# MicrobitBoardExtend.net
KiCad netlist of a schematic drawn in Altium Designer
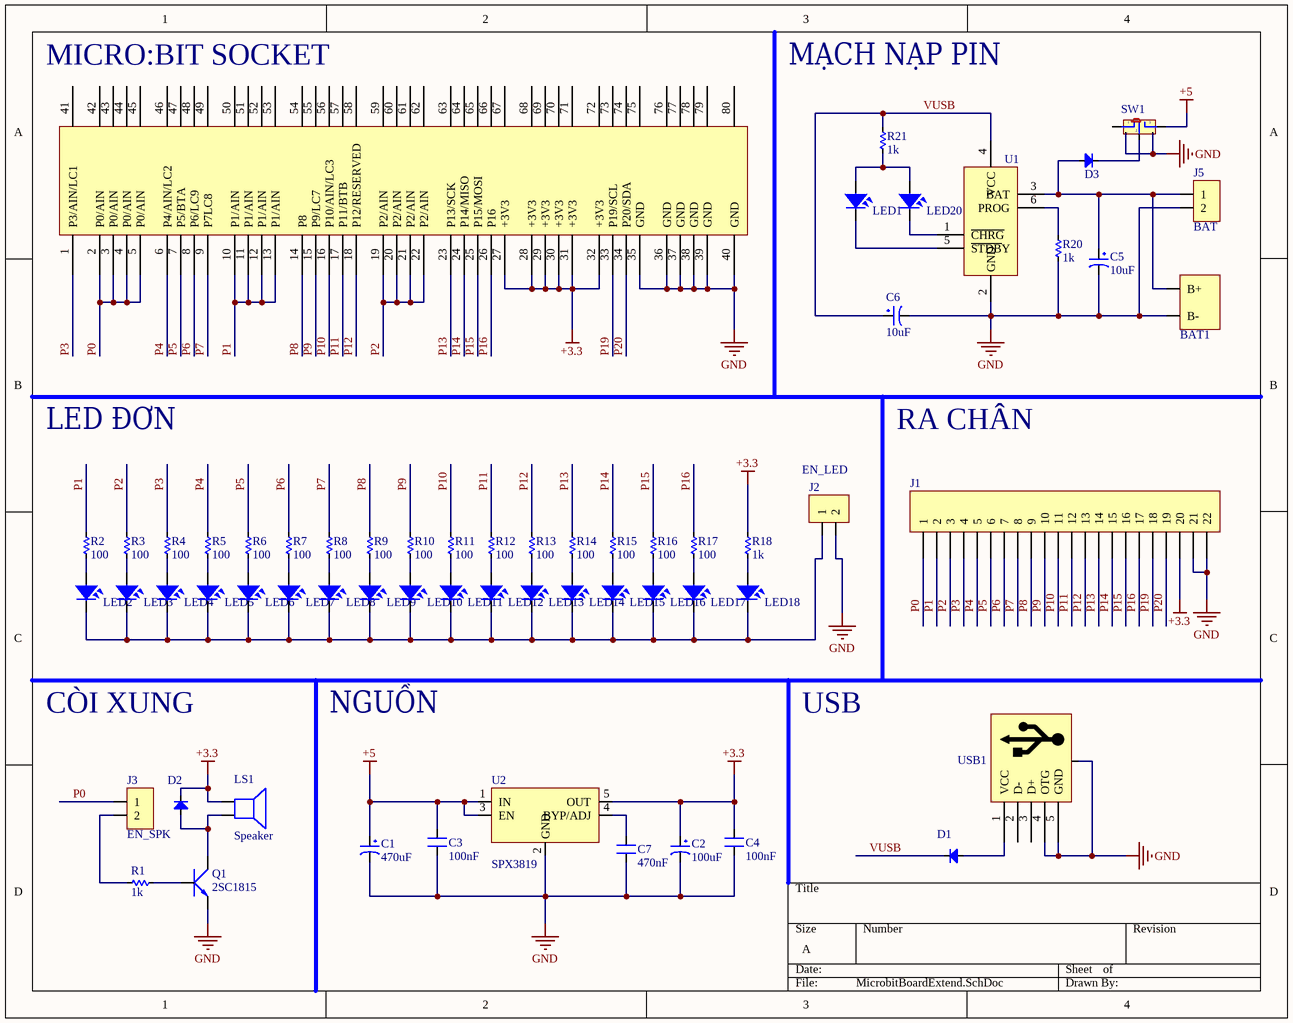
[diagram p0: MicrobitBoardExtend.SchDoc]

(export (version "E")
  (design (tool "Eeschema 10.0.6"))
  (components
    (comp (ref "BAT1")
      (value "BATERRY SOCKET")
      (footprint "BAT_SOCKET")
      (libsource (lib "User") (part "BAT_SOCKET"))
    )
    (comp (ref "BBC1")
      (value "BBC_SOCKET")
      (footprint "BBC_SK_DIP")
      (libsource (lib "microbit") (part "BBC_SOCKET"))
    )
    (comp (ref "C1")
      (value "470uF")
      (footprint "tu tantalum smd7343")
      (description "Dán")
      (libsource (lib "THU VIEN SCH_04042017_1") (part "Tu tantalum 470uF 10V SMD7343"))
    )
    (comp (ref "C2")
      (value "100uF")
      (footprint "tu tantalum smd3528")
      (description "Dán")
      (libsource (lib "THU VIEN SCH_04042017_1") (part "Tu tantalum 100uF 6.3V SMD3528"))
    )
    (comp (ref "C3") (value "100nF") (footprint "CN-SMD-0805") (libsource (lib "LIBRARY") (part "CN")))
    (comp (ref "C4") (value "100nF") (footprint "CN-SMD-0805") (libsource (lib "LIBRARY") (part "CN")))
    (comp (ref "C5")
      (value "10uF")
      (footprint "tu tantalum smd3528")
      (description "Dán")
      (libsource (lib "") (part "Tu tantalum 10uF 16V SMD3528_1"))
    )
    (comp (ref "C6")
      (value "10uF")
      (footprint "tu tantalum smd3528")
      (description "Dán")
      (libsource (lib "THU VIEN SCH_04042017_1") (part "Tu tantalum 10uF 16V SMD3528"))
    )
    (comp (ref "C7") (value "470nF") (footprint "CN-SMD-0805") (libsource (lib "LIBRARY") (part "CN")))
    (comp (ref "D1")
      (value "SS34")
      (footprint "DIO-SMD-123")
      (description "Default Diode")
      (fields (field (name "PUBLISHER") "Altium Limited"))
      (libsource (lib "LIBRARY") (part "Diode SMD"))
    )
    (comp (ref "D2")
      (value "SS34")
      (footprint "DIO-SMD-123")
      (description "Default Diode")
      (fields (field (name "PUBLISHER") "Altium Limited"))
      (libsource (lib "LIBRARY") (part "Diode SMD"))
    )
    (comp (ref "D3")
      (value "SS34")
      (footprint "DIO-SMD-123")
      (description "Default Diode")
      (fields (field (name "PUBLISHER") "Altium Limited"))
      (libsource (lib "LIBRARY") (part "Diode SMD"))
    )
    (comp (ref "J1")
      (value "JP22")
      (footprint "JP22-D1T")
      (description "WR-PHD 2.54 mm Angled Socket Header")
      (fields
        (field (name "MANUFACTURER") "Würth Elektronik eiSos GmbH")
        (field (name "PARTNO") "613022143121")
        (field (name "CREATED BY") "Karrer Zheng")
      )
      (libsource (lib "LIBRARY") (part "JP22"))
    )
    (comp (ref "J2")
      (value "EN_LED")
      (footprint "JP2-CLOSED")
      (description "WR-PHD 2.54 mm Angled Socket Header")
      (fields
        (field (name "MANUFACTURER") "Würth Elektronik eiSos GmbH")
        (field (name "PARTNO") "613002143121")
        (field (name "CREATED BY") "Karrer Zheng")
      )
      (libsource (lib "LIBRARY") (part "JP2"))
    )
    (comp (ref "J3")
      (value "EN_SPK")
      (footprint "JP2-CLOSED")
      (description "WR-PHD 2.54 mm Angled Socket Header")
      (fields
        (field (name "MANUFACTURER") "Würth Elektronik eiSos GmbH")
        (field (name "PARTNO") "613002143121")
        (field (name "CREATED BY") "Karrer Zheng")
      )
      (libsource (lib "") (part "JP2_1"))
    )
    (comp (ref "J5")
      (value "BAT")
      (footprint "JP2-D1T")
      (description "WR-PHD 2.54 mm Angled Socket Header")
      (fields
        (field (name "MANUFACTURER") "Würth Elektronik eiSos GmbH")
        (field (name "PARTNO") "613002143121")
        (field (name "CREATED BY") "Karrer Zheng")
      )
      (libsource (lib "") (part "JP2_1"))
    )
    (comp (ref "LED1") (value "F") (footprint "LED-0805-Blue") (libsource (lib "LIBRARY") (part "LED SMD")))
    (comp (ref "LED2")
      (value "LED")
      (footprint "LED-3MM-BLUE")
      (description "LED Single colour Green and Red")
      (libsource (lib "LIBRARY") (part "LED"))
    )
    (comp (ref "LED3")
      (value "LED")
      (footprint "LED-3MM-BLUE")
      (description "LED Single colour Green and Red")
      (libsource (lib "LIBRARY") (part "LED"))
    )
    (comp (ref "LED4")
      (value "LED")
      (footprint "LED-3MM-BLUE")
      (description "LED Single colour Green and Red")
      (libsource (lib "LIBRARY") (part "LED"))
    )
    (comp (ref "LED5")
      (value "LED")
      (footprint "LED-3MM-BLUE")
      (description "LED Single colour Green and Red")
      (libsource (lib "LIBRARY") (part "LED"))
    )
    (comp (ref "LED6")
      (value "LED")
      (footprint "LED-3MM-BLUE")
      (description "LED Single colour Green and Red")
      (libsource (lib "LIBRARY") (part "LED"))
    )
    (comp (ref "LED7")
      (value "LED")
      (footprint "LED-3MM-BLUE")
      (description "LED Single colour Green and Red")
      (libsource (lib "LIBRARY") (part "LED"))
    )
    (comp (ref "LED8")
      (value "LED")
      (footprint "LED-3MM-BLUE")
      (description "LED Single colour Green and Red")
      (libsource (lib "LIBRARY") (part "LED"))
    )
    (comp (ref "LED9")
      (value "LED")
      (footprint "LED-3MM-BLUE")
      (description "LED Single colour Green and Red")
      (libsource (lib "LIBRARY") (part "LED"))
    )
    (comp (ref "LED10")
      (value "LED")
      (footprint "LED-3MM-BLUE")
      (description "LED Single colour Green and Red")
      (libsource (lib "LIBRARY") (part "LED"))
    )
    (comp (ref "LED11")
      (value "LED")
      (footprint "LED-3MM-BLUE")
      (description "LED Single colour Green and Red")
      (libsource (lib "LIBRARY") (part "LED"))
    )
    (comp (ref "LED12")
      (value "LED")
      (footprint "LED-3MM-BLUE")
      (description "LED Single colour Green and Red")
      (libsource (lib "LIBRARY") (part "LED"))
    )
    (comp (ref "LED13")
      (value "LED")
      (footprint "LED-3MM-BLUE")
      (description "LED Single colour Green and Red")
      (libsource (lib "LIBRARY") (part "LED"))
    )
    (comp (ref "LED14")
      (value "LED")
      (footprint "LED-3MM-BLUE")
      (description "LED Single colour Green and Red")
      (libsource (lib "LIBRARY") (part "LED"))
    )
    (comp (ref "LED15")
      (value "LED")
      (footprint "LED-3MM-BLUE")
      (description "LED Single colour Green and Red")
      (libsource (lib "LIBRARY") (part "LED"))
    )
    (comp (ref "LED16")
      (value "LED")
      (footprint "LED-3MM-BLUE")
      (description "LED Single colour Green and Red")
      (libsource (lib "LIBRARY") (part "LED"))
    )
    (comp (ref "LED17")
      (value "LED")
      (footprint "LED-3MM-BLUE")
      (description "LED Single colour Green and Red")
      (libsource (lib "LIBRARY") (part "LED"))
    )
    (comp (ref "LED18")
      (value "PWR")
      (footprint "LED-0805-Blue")
      (libsource (lib "LIBRARY") (part "LED SMD"))
    )
    (comp (ref "LED20") (value "C") (footprint "LED-0805-Blue") (libsource (lib "LIBRARY") (part "LED SMD")))
    (comp (ref "LS1")
      (value "Speaker")
      (footprint "SPEAKER")
      (description "Loudspeaker")
      (fields (field (name "PUBLISHER") "Altium Limited"))
      (libsource (lib "LIBRARY") (part "Speaker"))
    )
    (comp (ref "Q1")
      (value "2SC1815")
      (footprint "SOT23-321")
      (description "NPN 600mW, ECB")
      (libsource (lib "LIBRARY") (part "2SC1815"))
    )
    (comp (ref "R1")
      (value "1k")
      (footprint "RES-SMD-0805")
      (description "Resistor")
      (fields
        (field (name "MANUFACTURER") "Generic Components")
        (field (name "PUBLISHER") "Altium Hobart Technology Centre")
      )
      (libsource (lib "LIBRARY") (part "Res-SMD"))
    )
    (comp (ref "R2")
      (value "100")
      (footprint "RES-SMD-0805")
      (description "Resistor")
      (fields
        (field (name "MANUFACTURER") "Generic Components")
        (field (name "PUBLISHER") "Altium Hobart Technology Centre")
      )
      (libsource (lib "LIBRARY") (part "Res-SMD"))
    )
    (comp (ref "R3")
      (value "100")
      (footprint "RES-SMD-0805")
      (description "Resistor")
      (fields
        (field (name "MANUFACTURER") "Generic Components")
        (field (name "PUBLISHER") "Altium Hobart Technology Centre")
      )
      (libsource (lib "LIBRARY") (part "Res-SMD"))
    )
    (comp (ref "R4")
      (value "100")
      (footprint "RES-SMD-0805")
      (description "Resistor")
      (fields
        (field (name "MANUFACTURER") "Generic Components")
        (field (name "PUBLISHER") "Altium Hobart Technology Centre")
      )
      (libsource (lib "LIBRARY") (part "Res-SMD"))
    )
    (comp (ref "R5")
      (value "100")
      (footprint "RES-SMD-0805")
      (description "Resistor")
      (fields
        (field (name "MANUFACTURER") "Generic Components")
        (field (name "PUBLISHER") "Altium Hobart Technology Centre")
      )
      (libsource (lib "LIBRARY") (part "Res-SMD"))
    )
    (comp (ref "R6")
      (value "100")
      (footprint "RES-SMD-0805")
      (description "Resistor")
      (fields
        (field (name "MANUFACTURER") "Generic Components")
        (field (name "PUBLISHER") "Altium Hobart Technology Centre")
      )
      (libsource (lib "LIBRARY") (part "Res-SMD"))
    )
    (comp (ref "R7")
      (value "100")
      (footprint "RES-SMD-0805")
      (description "Resistor")
      (fields
        (field (name "MANUFACTURER") "Generic Components")
        (field (name "PUBLISHER") "Altium Hobart Technology Centre")
      )
      (libsource (lib "LIBRARY") (part "Res-SMD"))
    )
    (comp (ref "R8")
      (value "100")
      (footprint "RES-SMD-0805")
      (description "Resistor")
      (fields
        (field (name "MANUFACTURER") "Generic Components")
        (field (name "PUBLISHER") "Altium Hobart Technology Centre")
      )
      (libsource (lib "LIBRARY") (part "Res-SMD"))
    )
    (comp (ref "R9")
      (value "100")
      (footprint "RES-SMD-0805")
      (description "Resistor")
      (fields
        (field (name "MANUFACTURER") "Generic Components")
        (field (name "PUBLISHER") "Altium Hobart Technology Centre")
      )
      (libsource (lib "LIBRARY") (part "Res-SMD"))
    )
    (comp (ref "R10")
      (value "100")
      (footprint "RES-SMD-0805")
      (description "Resistor")
      (fields
        (field (name "MANUFACTURER") "Generic Components")
        (field (name "PUBLISHER") "Altium Hobart Technology Centre")
      )
      (libsource (lib "LIBRARY") (part "Res-SMD"))
    )
    (comp (ref "R11")
      (value "100")
      (footprint "RES-SMD-0805")
      (description "Resistor")
      (fields
        (field (name "MANUFACTURER") "Generic Components")
        (field (name "PUBLISHER") "Altium Hobart Technology Centre")
      )
      (libsource (lib "LIBRARY") (part "Res-SMD"))
    )
    (comp (ref "R12")
      (value "100")
      (footprint "RES-SMD-0805")
      (description "Resistor")
      (fields
        (field (name "MANUFACTURER") "Generic Components")
        (field (name "PUBLISHER") "Altium Hobart Technology Centre")
      )
      (libsource (lib "LIBRARY") (part "Res-SMD"))
    )
    (comp (ref "R13")
      (value "100")
      (footprint "RES-SMD-0805")
      (description "Resistor")
      (fields
        (field (name "MANUFACTURER") "Generic Components")
        (field (name "PUBLISHER") "Altium Hobart Technology Centre")
      )
      (libsource (lib "LIBRARY") (part "Res-SMD"))
    )
    (comp (ref "R14")
      (value "100")
      (footprint "RES-SMD-0805")
      (description "Resistor")
      (fields
        (field (name "MANUFACTURER") "Generic Components")
        (field (name "PUBLISHER") "Altium Hobart Technology Centre")
      )
      (libsource (lib "LIBRARY") (part "Res-SMD"))
    )
    (comp (ref "R15")
      (value "100")
      (footprint "RES-SMD-0805")
      (description "Resistor")
      (fields
        (field (name "MANUFACTURER") "Generic Components")
        (field (name "PUBLISHER") "Altium Hobart Technology Centre")
      )
      (libsource (lib "LIBRARY") (part "Res-SMD"))
    )
    (comp (ref "R16")
      (value "100")
      (footprint "RES-SMD-0805")
      (description "Resistor")
      (fields
        (field (name "MANUFACTURER") "Generic Components")
        (field (name "PUBLISHER") "Altium Hobart Technology Centre")
      )
      (libsource (lib "LIBRARY") (part "Res-SMD"))
    )
    (comp (ref "R17")
      (value "100")
      (footprint "RES-SMD-0805")
      (description "Resistor")
      (fields
        (field (name "MANUFACTURER") "Generic Components")
        (field (name "PUBLISHER") "Altium Hobart Technology Centre")
      )
      (libsource (lib "LIBRARY") (part "Res-SMD"))
    )
    (comp (ref "R18")
      (value "1k")
      (footprint "RES-SMD-0805")
      (description "Resistor")
      (fields
        (field (name "MANUFACTURER") "Generic Components")
        (field (name "PUBLISHER") "Altium Hobart Technology Centre")
      )
      (libsource (lib "LIBRARY") (part "Res-SMD"))
    )
    (comp (ref "R20")
      (value "1k")
      (footprint "RES-SMD-0805")
      (description "Resistor")
      (fields
        (field (name "MANUFACTURER") "Generic Components")
        (field (name "PUBLISHER") "Altium Hobart Technology Centre")
      )
      (libsource (lib "LIBRARY") (part "Res-SMD"))
    )
    (comp (ref "R21")
      (value "1k")
      (footprint "RES-SMD-0805")
      (description "Resistor")
      (fields
        (field (name "MANUFACTURER") "Generic Components")
        (field (name "PUBLISHER") "Altium Hobart Technology Centre")
      )
      (libsource (lib "LIBRARY") (part "Res-SMD"))
    )
    (comp (ref "SW1")
      (value "SW102A")
      (footprint "SW102")
      (description "Switch 102 on Broad")
      (libsource (lib "MH_THU VIEN CHUAN 12-03-2015") (part "SW102A"))
    )
    (comp (ref "U1") (value "TP4057") (footprint "SOT23-6") (libsource (lib "TP4057") (part "TP4057")))
    (comp (ref "U2") (value "SPX3819") (footprint "SOT23-5") (libsource (lib "TP4057") (part "SPX3819")))
    (comp (ref "USB1") (value "PWR") (footprint "MicroUSB") (libsource (lib "User") (part "MicroUSB")))
  )
  (nets
    (net (code "1") (name "+3.3") (class "Default")
      (node (ref "BBC1") (pin "27") (pinfunction "+3V3_27") (pintype "passive"))
      (node (ref "BBC1") (pin "28") (pinfunction "+3V3_28") (pintype "passive"))
      (node (ref "BBC1") (pin "29") (pinfunction "+3V3_29") (pintype "passive"))
      (node (ref "BBC1") (pin "30") (pinfunction "+3V3_30") (pintype "passive"))
      (node (ref "BBC1") (pin "31") (pinfunction "+3V3_31") (pintype "passive"))
      (node (ref "BBC1") (pin "32") (pinfunction "+3V3_32") (pintype "passive"))
      (node (ref "C2") (pin "1") (pinfunction "1_1") (pintype "passive"))
      (node (ref "C4") (pin "1") (pinfunction "1_1") (pintype "passive"))
      (node (ref "D2") (pin "2") (pinfunction "K_2") (pintype "passive"))
      (node (ref "J1") (pin "20") (pinfunction "20_20") (pintype "passive"))
      (node (ref "LS1") (pin "1") (pinfunction "1_1") (pintype "passive"))
      (node (ref "R18") (pin "2") (pinfunction "2_2") (pintype "passive"))
      (node (ref "U2") (pin "5") (pinfunction "OUT_5") (pintype "passive"))
    )
    (net (code "2") (name "+5") (class "Default")
      (node (ref "C1") (pin "1") (pinfunction "1_1") (pintype "passive"))
      (node (ref "C3") (pin "1") (pinfunction "1_1") (pintype "passive"))
      (node (ref "SW1") (pin "3") (pinfunction "3_3") (pintype "passive"))
      (node (ref "U2") (pin "1") (pinfunction "IN_1") (pintype "passive"))
      (node (ref "U2") (pin "3") (pinfunction "EN_3") (pintype "passive"))
    )
    (net (code "3") (name "/P0") (class "Default")
      (node (ref "BBC1") (pin "2") (pinfunction "P0/AIN_2") (pintype "passive"))
      (node (ref "BBC1") (pin "3") (pinfunction "P0/AIN_3") (pintype "passive"))
      (node (ref "BBC1") (pin "4") (pinfunction "P0/AIN_4") (pintype "passive"))
      (node (ref "BBC1") (pin "5") (pinfunction "P0/AIN_5") (pintype "passive"))
      (node (ref "J1") (pin "1") (pinfunction "1_1") (pintype "passive"))
      (node (ref "J3") (pin "1") (pinfunction "1_1") (pintype "passive"))
    )
    (net (code "4") (name "/P1") (class "Default")
      (node (ref "BBC1") (pin "10") (pinfunction "P1/AIN_10") (pintype "passive"))
      (node (ref "BBC1") (pin "11") (pinfunction "P1/AIN_11") (pintype "passive"))
      (node (ref "BBC1") (pin "12") (pinfunction "P1/AIN_12") (pintype "passive"))
      (node (ref "BBC1") (pin "13") (pinfunction "P1/AIN_13") (pintype "passive"))
      (node (ref "J1") (pin "2") (pinfunction "2_2") (pintype "passive"))
      (node (ref "R2") (pin "2") (pinfunction "2_2") (pintype "passive"))
    )
    (net (code "5") (name "/P2") (class "Default")
      (node (ref "BBC1") (pin "19") (pinfunction "P2/AIN_19") (pintype "passive"))
      (node (ref "BBC1") (pin "20") (pinfunction "P2/AIN_20") (pintype "passive"))
      (node (ref "BBC1") (pin "21") (pinfunction "P2/AIN_21") (pintype "passive"))
      (node (ref "BBC1") (pin "22") (pinfunction "P2/AIN_22") (pintype "passive"))
      (node (ref "J1") (pin "3") (pinfunction "3_3") (pintype "passive"))
      (node (ref "R3") (pin "2") (pinfunction "2_2") (pintype "passive"))
    )
    (net (code "6") (name "/P3") (class "Default")
      (node (ref "BBC1") (pin "1") (pinfunction "P3/AIN/LC1_1") (pintype "passive"))
      (node (ref "J1") (pin "4") (pinfunction "4_4") (pintype "passive"))
      (node (ref "R4") (pin "2") (pinfunction "2_2") (pintype "passive"))
    )
    (net (code "7") (name "/P4") (class "Default")
      (node (ref "BBC1") (pin "6") (pinfunction "P4/AIN/LC2_6") (pintype "passive"))
      (node (ref "J1") (pin "5") (pinfunction "5_5") (pintype "passive"))
      (node (ref "R5") (pin "2") (pinfunction "2_2") (pintype "passive"))
    )
    (net (code "8") (name "/P5") (class "Default")
      (node (ref "BBC1") (pin "7") (pinfunction "P5/BTA_7") (pintype "passive"))
      (node (ref "J1") (pin "6") (pinfunction "6_6") (pintype "passive"))
      (node (ref "R6") (pin "2") (pinfunction "2_2") (pintype "passive"))
    )
    (net (code "9") (name "/P6") (class "Default")
      (node (ref "BBC1") (pin "8") (pinfunction "P6/LC9_8") (pintype "passive"))
      (node (ref "J1") (pin "7") (pinfunction "7_7") (pintype "passive"))
      (node (ref "R7") (pin "2") (pinfunction "2_2") (pintype "passive"))
    )
    (net (code "10") (name "/P7") (class "Default")
      (node (ref "BBC1") (pin "9") (pinfunction "P7LC8_9") (pintype "passive"))
      (node (ref "J1") (pin "8") (pinfunction "8_8") (pintype "passive"))
      (node (ref "R8") (pin "2") (pinfunction "2_2") (pintype "passive"))
    )
    (net (code "11") (name "/P8") (class "Default")
      (node (ref "BBC1") (pin "14") (pinfunction "P8_14") (pintype "passive"))
      (node (ref "J1") (pin "9") (pinfunction "9_9") (pintype "passive"))
      (node (ref "R9") (pin "2") (pinfunction "2_2") (pintype "passive"))
    )
    (net (code "12") (name "/P9") (class "Default")
      (node (ref "BBC1") (pin "15") (pinfunction "P9/LC7_15") (pintype "passive"))
      (node (ref "J1") (pin "10") (pinfunction "10_10") (pintype "passive"))
      (node (ref "R10") (pin "2") (pinfunction "2_2") (pintype "passive"))
    )
    (net (code "13") (name "/P10") (class "Default")
      (node (ref "BBC1") (pin "16") (pinfunction "P10/AIN/LC3_16") (pintype "passive"))
      (node (ref "J1") (pin "11") (pinfunction "11_11") (pintype "passive"))
      (node (ref "R11") (pin "2") (pinfunction "2_2") (pintype "passive"))
    )
    (net (code "14") (name "/P11") (class "Default")
      (node (ref "BBC1") (pin "17") (pinfunction "P11/BTB_17") (pintype "passive"))
      (node (ref "J1") (pin "12") (pinfunction "12_12") (pintype "passive"))
      (node (ref "R12") (pin "2") (pinfunction "2_2") (pintype "passive"))
    )
    (net (code "15") (name "/P12") (class "Default")
      (node (ref "BBC1") (pin "18") (pinfunction "P12/RESERVED_18") (pintype "passive"))
      (node (ref "J1") (pin "13") (pinfunction "13_13") (pintype "passive"))
      (node (ref "R13") (pin "2") (pinfunction "2_2") (pintype "passive"))
    )
    (net (code "16") (name "/P13") (class "Default")
      (node (ref "BBC1") (pin "23") (pinfunction "P13/SCK_23") (pintype "passive"))
      (node (ref "J1") (pin "14") (pinfunction "14_14") (pintype "passive"))
      (node (ref "R14") (pin "2") (pinfunction "2_2") (pintype "passive"))
    )
    (net (code "17") (name "/P14") (class "Default")
      (node (ref "BBC1") (pin "24") (pinfunction "P14/MISO_24") (pintype "passive"))
      (node (ref "J1") (pin "15") (pinfunction "15_15") (pintype "passive"))
      (node (ref "R15") (pin "2") (pinfunction "2_2") (pintype "passive"))
    )
    (net (code "18") (name "/P15") (class "Default")
      (node (ref "BBC1") (pin "25") (pinfunction "P15/MOSI_25") (pintype "passive"))
      (node (ref "J1") (pin "16") (pinfunction "16_16") (pintype "passive"))
      (node (ref "R16") (pin "2") (pinfunction "2_2") (pintype "passive"))
    )
    (net (code "19") (name "/P16") (class "Default")
      (node (ref "BBC1") (pin "26") (pinfunction "P16_26") (pintype "passive"))
      (node (ref "J1") (pin "17") (pinfunction "17_17") (pintype "passive"))
      (node (ref "R17") (pin "2") (pinfunction "2_2") (pintype "passive"))
    )
    (net (code "20") (name "/P19") (class "Default")
      (node (ref "BBC1") (pin "33") (pinfunction "P19/SCL_33") (pintype "passive"))
      (node (ref "J1") (pin "18") (pinfunction "18_18") (pintype "passive"))
    )
    (net (code "21") (name "/P20") (class "Default")
      (node (ref "BBC1") (pin "34") (pinfunction "P20/SDA_34") (pintype "passive"))
      (node (ref "J1") (pin "19") (pinfunction "19_19") (pintype "passive"))
    )
    (net (code "22") (name "/VUSB") (class "Default")
      (node (ref "C6") (pin "1") (pinfunction "1_1") (pintype "passive"))
      (node (ref "D1") (pin "2") (pinfunction "K_2") (pintype "passive"))
      (node (ref "R21") (pin "2") (pinfunction "2_2") (pintype "passive"))
      (node (ref "U1") (pin "4") (pinfunction "VCC_4") (pintype "passive"))
    )
    (net (code "23") (name "GND") (class "Default")
      (node (ref "BAT1") (pin "2") (pinfunction "B-_2") (pintype "passive"))
      (node (ref "BBC1") (pin "35") (pinfunction "GND_35") (pintype "passive"))
      (node (ref "BBC1") (pin "36") (pinfunction "GND_36") (pintype "passive"))
      (node (ref "BBC1") (pin "37") (pinfunction "GND_37") (pintype "passive"))
      (node (ref "BBC1") (pin "38") (pinfunction "GND_38") (pintype "passive"))
      (node (ref "BBC1") (pin "39") (pinfunction "GND_39") (pintype "passive"))
      (node (ref "BBC1") (pin "40") (pinfunction "GND_40") (pintype "passive"))
      (node (ref "C1") (pin "2") (pinfunction "2_2") (pintype "passive"))
      (node (ref "C2") (pin "2") (pinfunction "2_2") (pintype "passive"))
      (node (ref "C3") (pin "2") (pinfunction "2_2") (pintype "passive"))
      (node (ref "C4") (pin "2") (pinfunction "2_2") (pintype "passive"))
      (node (ref "C5") (pin "2") (pinfunction "2_2") (pintype "passive"))
      (node (ref "C6") (pin "2") (pinfunction "2_2") (pintype "passive"))
      (node (ref "C7") (pin "2") (pinfunction "2_2") (pintype "passive"))
      (node (ref "J1") (pin "21") (pinfunction "21_21") (pintype "passive"))
      (node (ref "J1") (pin "22") (pinfunction "22_22") (pintype "passive"))
      (node (ref "J2") (pin "2") (pinfunction "2_2") (pintype "passive"))
      (node (ref "J5") (pin "2") (pinfunction "2_2") (pintype "passive"))
      (node (ref "Q1") (pin "1") (pinfunction "E_1") (pintype "passive"))
      (node (ref "R20") (pin "1") (pinfunction "1_1") (pintype "passive"))
      (node (ref "SW1") (pin "4") (pinfunction "4_4") (pintype "passive"))
      (node (ref "SW1") (pin "5") (pinfunction "5_5") (pintype "passive"))
      (node (ref "U1") (pin "2") (pinfunction "GND_2") (pintype "passive"))
      (node (ref "U2") (pin "2") (pinfunction "GND_2") (pintype "passive"))
      (node (ref "USB1") (pin "0") (pinfunction "GND_0") (pintype "passive"))
      (node (ref "USB1") (pin "4") (pinfunction "OTG_4") (pintype "passive"))
      (node (ref "USB1") (pin "5") (pinfunction "GND_5") (pintype "passive"))
    )
    (net (code "24") (name "Net-(BAT1-B+)") (class "Default")
      (node (ref "BAT1") (pin "1") (pinfunction "B+_1") (pintype "passive"))
      (node (ref "C5") (pin "1") (pinfunction "1_1") (pintype "passive"))
      (node (ref "D3") (pin "1") (pinfunction "A_1") (pintype "passive"))
      (node (ref "J5") (pin "1") (pinfunction "1_1") (pintype "passive"))
      (node (ref "U1") (pin "3") (pinfunction "BAT_3") (pintype "passive"))
    )
    (net (code "25") (name "Net-(D1-A)") (class "Default")
      (node (ref "D1") (pin "1") (pinfunction "A_1") (pintype "passive"))
      (node (ref "USB1") (pin "1") (pinfunction "VCC_1") (pintype "passive"))
    )
    (net (code "26") (name "Net-(D2-A)") (class "Default")
      (node (ref "D2") (pin "1") (pinfunction "A_1") (pintype "passive"))
      (node (ref "LS1") (pin "2") (pinfunction "2_2") (pintype "passive"))
      (node (ref "Q1") (pin "2") (pinfunction "C_2") (pintype "passive"))
    )
    (net (code "27") (name "Net-(D3-K)") (class "Default")
      (node (ref "D3") (pin "2") (pinfunction "K_2") (pintype "passive"))
      (node (ref "SW1") (pin "2") (pinfunction "2_2") (pintype "passive"))
    )
    (net (code "28") (name "Net-(J2-Pad1)") (class "Default")
      (node (ref "J2") (pin "1") (pinfunction "1_1") (pintype "passive"))
      (node (ref "LED10") (pin "2") (pinfunction "2_2") (pintype "passive"))
      (node (ref "LED11") (pin "2") (pinfunction "2_2") (pintype "passive"))
      (node (ref "LED12") (pin "2") (pinfunction "2_2") (pintype "passive"))
      (node (ref "LED13") (pin "2") (pinfunction "2_2") (pintype "passive"))
      (node (ref "LED14") (pin "2") (pinfunction "2_2") (pintype "passive"))
      (node (ref "LED15") (pin "2") (pinfunction "2_2") (pintype "passive"))
      (node (ref "LED16") (pin "2") (pinfunction "2_2") (pintype "passive"))
      (node (ref "LED17") (pin "2") (pinfunction "2_2") (pintype "passive"))
      (node (ref "LED18") (pin "2") (pinfunction "2_2") (pintype "passive"))
      (node (ref "LED2") (pin "2") (pinfunction "2_2") (pintype "passive"))
      (node (ref "LED3") (pin "2") (pinfunction "2_2") (pintype "passive"))
      (node (ref "LED4") (pin "2") (pinfunction "2_2") (pintype "passive"))
      (node (ref "LED5") (pin "2") (pinfunction "2_2") (pintype "passive"))
      (node (ref "LED6") (pin "2") (pinfunction "2_2") (pintype "passive"))
      (node (ref "LED7") (pin "2") (pinfunction "2_2") (pintype "passive"))
      (node (ref "LED8") (pin "2") (pinfunction "2_2") (pintype "passive"))
      (node (ref "LED9") (pin "2") (pinfunction "2_2") (pintype "passive"))
    )
    (net (code "29") (name "Net-(J3-Pad2)") (class "Default")
      (node (ref "J3") (pin "2") (pinfunction "2_2") (pintype "passive"))
      (node (ref "R1") (pin "2") (pinfunction "2_2") (pintype "passive"))
    )
    (net (code "30") (name "Net-(LED1-Pad1)") (class "Default")
      (node (ref "LED1") (pin "1") (pinfunction "1_1") (pintype "passive"))
      (node (ref "LED20") (pin "1") (pinfunction "1_1") (pintype "passive"))
      (node (ref "R21") (pin "1") (pinfunction "1_1") (pintype "passive"))
    )
    (net (code "31") (name "Net-(LED2-Pad1)") (class "Default")
      (node (ref "LED2") (pin "1") (pinfunction "1_1") (pintype "passive"))
      (node (ref "R2") (pin "1") (pinfunction "1_1") (pintype "passive"))
    )
    (net (code "32") (name "Net-(LED3-Pad1)") (class "Default")
      (node (ref "LED3") (pin "1") (pinfunction "1_1") (pintype "passive"))
      (node (ref "R3") (pin "1") (pinfunction "1_1") (pintype "passive"))
    )
    (net (code "33") (name "Net-(LED4-Pad1)") (class "Default")
      (node (ref "LED4") (pin "1") (pinfunction "1_1") (pintype "passive"))
      (node (ref "R4") (pin "1") (pinfunction "1_1") (pintype "passive"))
    )
    (net (code "34") (name "Net-(LED5-Pad1)") (class "Default")
      (node (ref "LED5") (pin "1") (pinfunction "1_1") (pintype "passive"))
      (node (ref "R5") (pin "1") (pinfunction "1_1") (pintype "passive"))
    )
    (net (code "35") (name "Net-(LED6-Pad1)") (class "Default")
      (node (ref "LED6") (pin "1") (pinfunction "1_1") (pintype "passive"))
      (node (ref "R6") (pin "1") (pinfunction "1_1") (pintype "passive"))
    )
    (net (code "36") (name "Net-(LED7-Pad1)") (class "Default")
      (node (ref "LED7") (pin "1") (pinfunction "1_1") (pintype "passive"))
      (node (ref "R7") (pin "1") (pinfunction "1_1") (pintype "passive"))
    )
    (net (code "37") (name "Net-(LED8-Pad1)") (class "Default")
      (node (ref "LED8") (pin "1") (pinfunction "1_1") (pintype "passive"))
      (node (ref "R8") (pin "1") (pinfunction "1_1") (pintype "passive"))
    )
    (net (code "38") (name "Net-(LED9-Pad1)") (class "Default")
      (node (ref "LED9") (pin "1") (pinfunction "1_1") (pintype "passive"))
      (node (ref "R9") (pin "1") (pinfunction "1_1") (pintype "passive"))
    )
    (net (code "39") (name "Net-(LED10-Pad1)") (class "Default")
      (node (ref "LED10") (pin "1") (pinfunction "1_1") (pintype "passive"))
      (node (ref "R10") (pin "1") (pinfunction "1_1") (pintype "passive"))
    )
    (net (code "40") (name "Net-(LED11-Pad1)") (class "Default")
      (node (ref "LED11") (pin "1") (pinfunction "1_1") (pintype "passive"))
      (node (ref "R11") (pin "1") (pinfunction "1_1") (pintype "passive"))
    )
    (net (code "41") (name "Net-(LED12-Pad1)") (class "Default")
      (node (ref "LED12") (pin "1") (pinfunction "1_1") (pintype "passive"))
      (node (ref "R12") (pin "1") (pinfunction "1_1") (pintype "passive"))
    )
    (net (code "42") (name "Net-(LED13-Pad1)") (class "Default")
      (node (ref "LED13") (pin "1") (pinfunction "1_1") (pintype "passive"))
      (node (ref "R13") (pin "1") (pinfunction "1_1") (pintype "passive"))
    )
    (net (code "43") (name "Net-(LED14-Pad1)") (class "Default")
      (node (ref "LED14") (pin "1") (pinfunction "1_1") (pintype "passive"))
      (node (ref "R14") (pin "1") (pinfunction "1_1") (pintype "passive"))
    )
    (net (code "44") (name "Net-(LED15-Pad1)") (class "Default")
      (node (ref "LED15") (pin "1") (pinfunction "1_1") (pintype "passive"))
      (node (ref "R15") (pin "1") (pinfunction "1_1") (pintype "passive"))
    )
    (net (code "45") (name "Net-(LED16-Pad1)") (class "Default")
      (node (ref "LED16") (pin "1") (pinfunction "1_1") (pintype "passive"))
      (node (ref "R16") (pin "1") (pinfunction "1_1") (pintype "passive"))
    )
    (net (code "46") (name "Net-(LED17-Pad1)") (class "Default")
      (node (ref "LED17") (pin "1") (pinfunction "1_1") (pintype "passive"))
      (node (ref "R17") (pin "1") (pinfunction "1_1") (pintype "passive"))
    )
    (net (code "47") (name "Net-(LED18-Pad1)") (class "Default")
      (node (ref "LED18") (pin "1") (pinfunction "1_1") (pintype "passive"))
      (node (ref "R18") (pin "1") (pinfunction "1_1") (pintype "passive"))
    )
    (net (code "48") (name "Net-(Q1-B)") (class "Default")
      (node (ref "Q1") (pin "3") (pinfunction "B_3") (pintype "passive"))
      (node (ref "R1") (pin "1") (pinfunction "1_1") (pintype "passive"))
    )
    (net (code "49") (name "Net-(U1-PROG)") (class "Default")
      (node (ref "R20") (pin "2") (pinfunction "2_2") (pintype "passive"))
      (node (ref "U1") (pin "6") (pinfunction "PROG_6") (pintype "passive"))
    )
    (net (code "50") (name "Net-(U1-~{CHRG})") (class "Default")
      (node (ref "LED20") (pin "2") (pinfunction "2_2") (pintype "passive"))
      (node (ref "U1") (pin "1") (pinfunction "~{CHRG}_1") (pintype "passive"))
    )
    (net (code "51") (name "Net-(U1-~{STDB}Y)") (class "Default")
      (node (ref "LED1") (pin "2") (pinfunction "2_2") (pintype "passive"))
      (node (ref "U1") (pin "5") (pinfunction "~{STDB}Y_5") (pintype "passive"))
    )
    (net (code "52") (name "Net-(U2-BYP{slash}ADJ)") (class "Default")
      (node (ref "C7") (pin "1") (pinfunction "1_1") (pintype "passive"))
      (node (ref "U2") (pin "4") (pinfunction "BYP/ADJ_4") (pintype "passive"))
    )
    (net (code "53") (name "unconnected-(BBC1-+3V3-Pad67)") (class "Default")
      (node (ref "BBC1") (pin "67") (pinfunction "+3V3_67") (pintype "passive"))
    )
    (net (code "54") (name "unconnected-(BBC1-+3V3-Pad68)") (class "Default")
      (node (ref "BBC1") (pin "68") (pinfunction "+3V3_68") (pintype "passive"))
    )
    (net (code "55") (name "unconnected-(BBC1-+3V3-Pad69)") (class "Default")
      (node (ref "BBC1") (pin "69") (pinfunction "+3V3_69") (pintype "passive"))
    )
    (net (code "56") (name "unconnected-(BBC1-+3V3-Pad70)") (class "Default")
      (node (ref "BBC1") (pin "70") (pinfunction "+3V3_70") (pintype "passive"))
    )
    (net (code "57") (name "unconnected-(BBC1-+3V3-Pad71)") (class "Default")
      (node (ref "BBC1") (pin "71") (pinfunction "+3V3_71") (pintype "passive"))
    )
    (net (code "58") (name "unconnected-(BBC1-+3V3-Pad72)") (class "Default")
      (node (ref "BBC1") (pin "72") (pinfunction "+3V3_72") (pintype "passive"))
    )
    (net (code "59") (name "unconnected-(BBC1-GND-Pad75)") (class "Default")
      (node (ref "BBC1") (pin "75") (pinfunction "GND_75") (pintype "passive"))
    )
    (net (code "60") (name "unconnected-(BBC1-GND-Pad76)") (class "Default")
      (node (ref "BBC1") (pin "76") (pinfunction "GND_76") (pintype "passive"))
    )
    (net (code "61") (name "unconnected-(BBC1-GND-Pad77)") (class "Default")
      (node (ref "BBC1") (pin "77") (pinfunction "GND_77") (pintype "passive"))
    )
    (net (code "62") (name "unconnected-(BBC1-GND-Pad78)") (class "Default")
      (node (ref "BBC1") (pin "78") (pinfunction "GND_78") (pintype "passive"))
    )
    (net (code "63") (name "unconnected-(BBC1-GND-Pad79)") (class "Default")
      (node (ref "BBC1") (pin "79") (pinfunction "GND_79") (pintype "passive"))
    )
    (net (code "64") (name "unconnected-(BBC1-GND-Pad80)") (class "Default")
      (node (ref "BBC1") (pin "80") (pinfunction "GND_80") (pintype "passive"))
    )
    (net (code "65") (name "unconnected-(BBC1-P0-Pad42)") (class "Default")
      (node (ref "BBC1") (pin "42") (pinfunction "P0_42") (pintype "passive"))
    )
    (net (code "66") (name "unconnected-(BBC1-P0-Pad43)") (class "Default")
      (node (ref "BBC1") (pin "43") (pinfunction "P0_43") (pintype "passive"))
    )
    (net (code "67") (name "unconnected-(BBC1-P0-Pad44)") (class "Default")
      (node (ref "BBC1") (pin "44") (pinfunction "P0_44") (pintype "passive"))
    )
    (net (code "68") (name "unconnected-(BBC1-P0-Pad45)") (class "Default")
      (node (ref "BBC1") (pin "45") (pinfunction "P0_45") (pintype "passive"))
    )
    (net (code "69") (name "unconnected-(BBC1-P1-Pad50)") (class "Default")
      (node (ref "BBC1") (pin "50") (pinfunction "P1_50") (pintype "passive"))
    )
    (net (code "70") (name "unconnected-(BBC1-P1-Pad51)") (class "Default")
      (node (ref "BBC1") (pin "51") (pinfunction "P1_51") (pintype "passive"))
    )
    (net (code "71") (name "unconnected-(BBC1-P1-Pad52)") (class "Default")
      (node (ref "BBC1") (pin "52") (pinfunction "P1_52") (pintype "passive"))
    )
    (net (code "72") (name "unconnected-(BBC1-P1-Pad53)") (class "Default")
      (node (ref "BBC1") (pin "53") (pinfunction "P1_53") (pintype "passive"))
    )
    (net (code "73") (name "unconnected-(BBC1-P2-Pad59)") (class "Default")
      (node (ref "BBC1") (pin "59") (pinfunction "P2_59") (pintype "passive"))
    )
    (net (code "74") (name "unconnected-(BBC1-P2-Pad60)") (class "Default")
      (node (ref "BBC1") (pin "60") (pinfunction "P2_60") (pintype "passive"))
    )
    (net (code "75") (name "unconnected-(BBC1-P2-Pad61)") (class "Default")
      (node (ref "BBC1") (pin "61") (pinfunction "P2_61") (pintype "passive"))
    )
    (net (code "76") (name "unconnected-(BBC1-P2-Pad62)") (class "Default")
      (node (ref "BBC1") (pin "62") (pinfunction "P2_62") (pintype "passive"))
    )
    (net (code "77") (name "unconnected-(BBC1-P3-Pad41)") (class "Default")
      (node (ref "BBC1") (pin "41") (pinfunction "P3_41") (pintype "passive"))
    )
    (net (code "78") (name "unconnected-(BBC1-P4-Pad46)") (class "Default")
      (node (ref "BBC1") (pin "46") (pinfunction "P4_46") (pintype "passive"))
    )
    (net (code "79") (name "unconnected-(BBC1-P5-Pad47)") (class "Default")
      (node (ref "BBC1") (pin "47") (pinfunction "P5_47") (pintype "passive"))
    )
    (net (code "80") (name "unconnected-(BBC1-P6-Pad48)") (class "Default")
      (node (ref "BBC1") (pin "48") (pinfunction "P6_48") (pintype "passive"))
    )
    (net (code "81") (name "unconnected-(BBC1-P7-Pad49)") (class "Default")
      (node (ref "BBC1") (pin "49") (pinfunction "P7_49") (pintype "passive"))
    )
    (net (code "82") (name "unconnected-(BBC1-P8-Pad54)") (class "Default")
      (node (ref "BBC1") (pin "54") (pinfunction "P8_54") (pintype "passive"))
    )
    (net (code "83") (name "unconnected-(BBC1-P9-Pad55)") (class "Default")
      (node (ref "BBC1") (pin "55") (pinfunction "P9_55") (pintype "passive"))
    )
    (net (code "84") (name "unconnected-(BBC1-P10-Pad56)") (class "Default")
      (node (ref "BBC1") (pin "56") (pinfunction "P10_56") (pintype "passive"))
    )
    (net (code "85") (name "unconnected-(BBC1-P11-Pad57)") (class "Default")
      (node (ref "BBC1") (pin "57") (pinfunction "P11_57") (pintype "passive"))
    )
    (net (code "86") (name "unconnected-(BBC1-P12-Pad58)") (class "Default")
      (node (ref "BBC1") (pin "58") (pinfunction "P12_58") (pintype "passive"))
    )
    (net (code "87") (name "unconnected-(BBC1-P13-Pad63)") (class "Default")
      (node (ref "BBC1") (pin "63") (pinfunction "P13_63") (pintype "passive"))
    )
    (net (code "88") (name "unconnected-(BBC1-P14-Pad64)") (class "Default")
      (node (ref "BBC1") (pin "64") (pinfunction "P14_64") (pintype "passive"))
    )
    (net (code "89") (name "unconnected-(BBC1-P15-Pad65)") (class "Default")
      (node (ref "BBC1") (pin "65") (pinfunction "P15_65") (pintype "passive"))
    )
    (net (code "90") (name "unconnected-(BBC1-P16-Pad66)") (class "Default")
      (node (ref "BBC1") (pin "66") (pinfunction "P16_66") (pintype "passive"))
    )
    (net (code "91") (name "unconnected-(BBC1-P19-Pad73)") (class "Default")
      (node (ref "BBC1") (pin "73") (pinfunction "P19_73") (pintype "passive"))
    )
    (net (code "92") (name "unconnected-(BBC1-P20-Pad74)") (class "Default")
      (node (ref "BBC1") (pin "74") (pinfunction "P20_74") (pintype "passive"))
    )
    (net (code "93") (name "unconnected-(SW1-Pad1)") (class "Default")
      (node (ref "SW1") (pin "1") (pinfunction "1_1") (pintype "passive"))
    )
    (net (code "94") (name "unconnected-(USB1-D+-Pad3)") (class "Default")
      (node (ref "USB1") (pin "3") (pinfunction "D+_3") (pintype "passive"))
    )
    (net (code "95") (name "unconnected-(USB1-D--Pad2)") (class "Default")
      (node (ref "USB1") (pin "2") (pinfunction "D-_2") (pintype "passive"))
    )
  )
)
